# esp8266-board.net
KiCad netlist of a schematic drawn in EAGLE
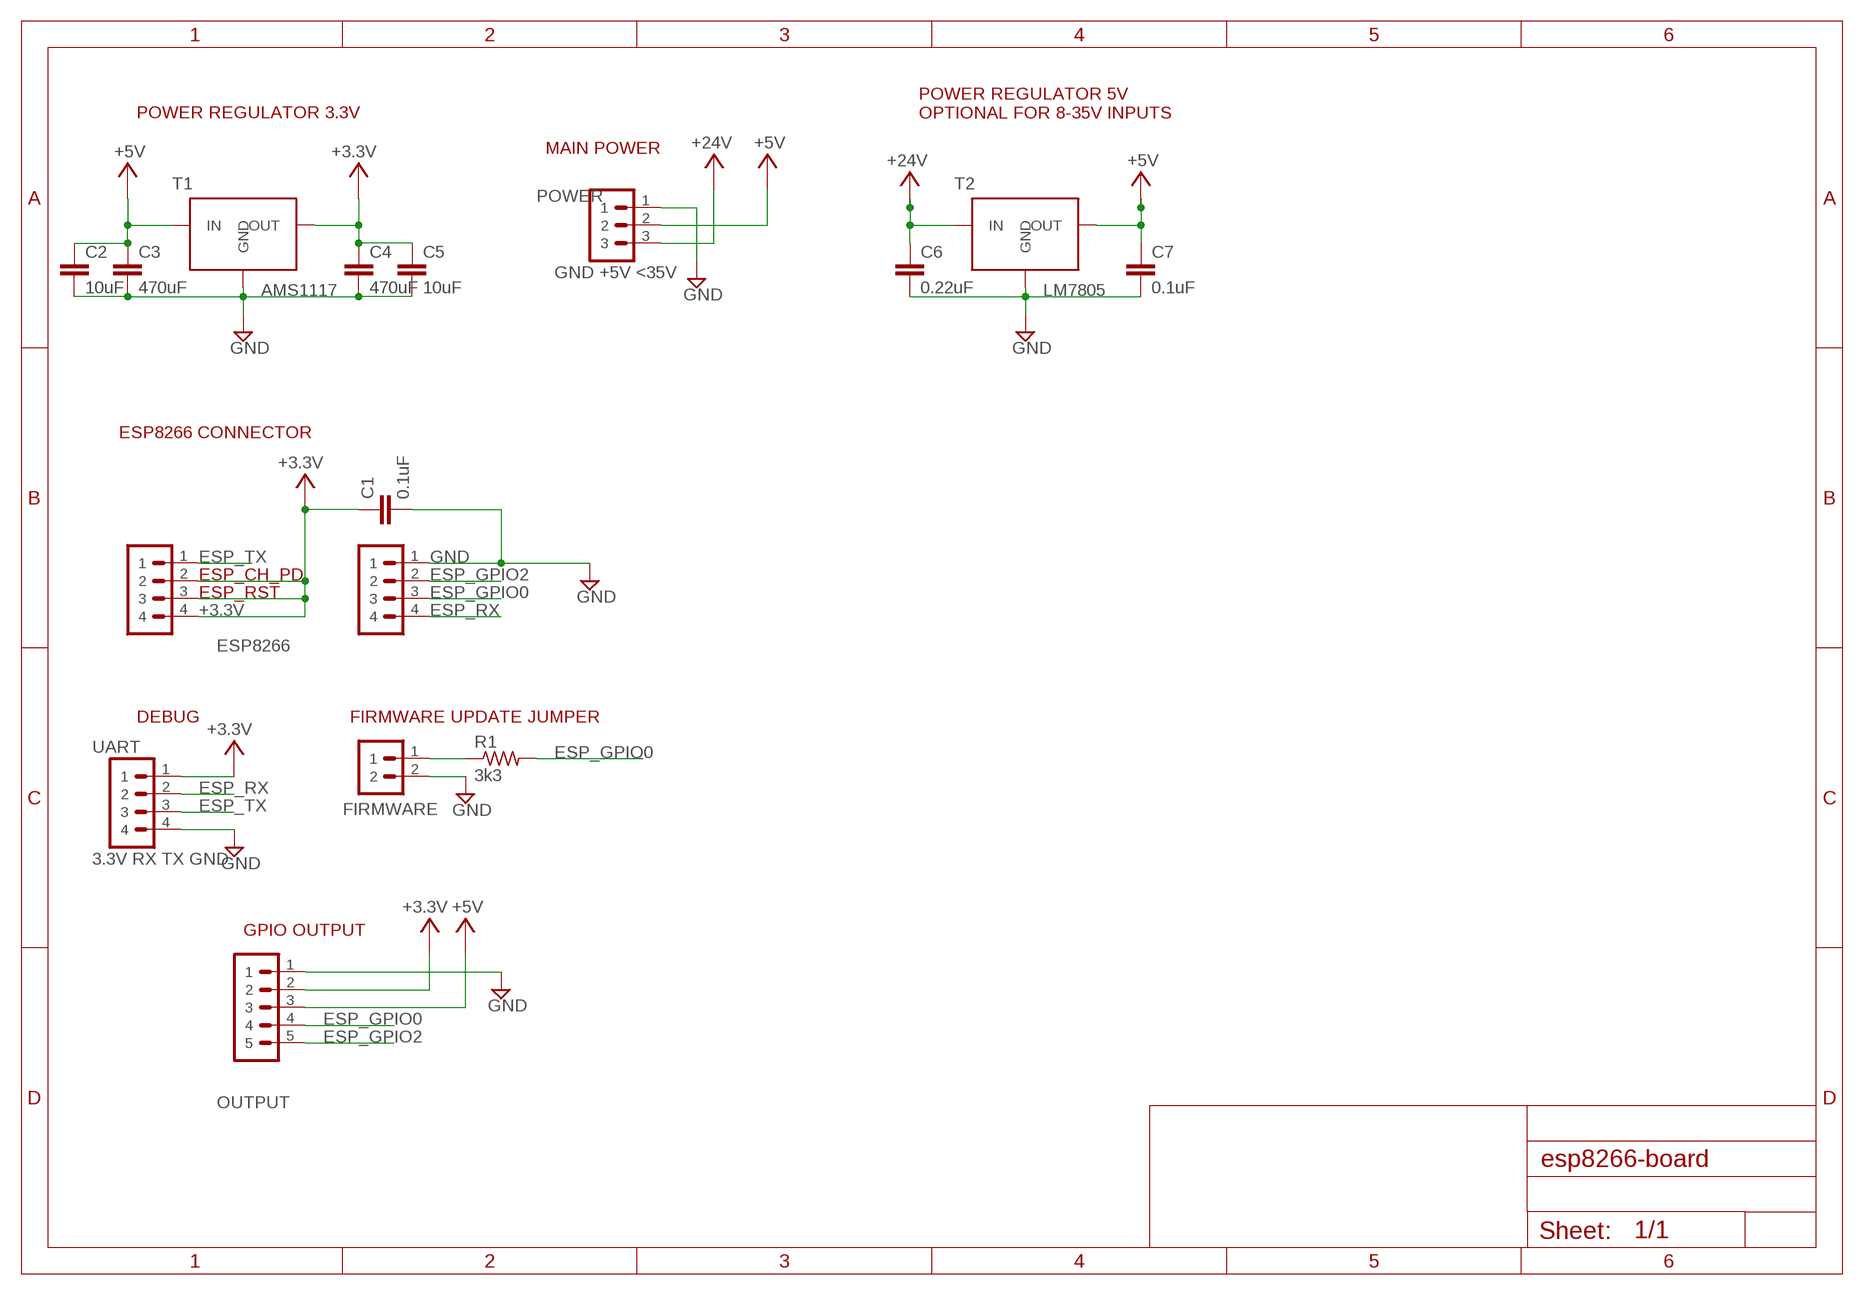
[diagram p0: schematic, sheet 1]

(export (version "E")
  (design (tool "Eeschema 10.0.6"))
  (components
    (comp (ref "C1")
      (value "0.1uF")
      (footprint "eagle-import:C2.5-2")
      (libsource (lib "eagle-import") (part "C2.5/2"))
    )
    (comp (ref "C2")
      (value "10uF")
      (footprint "eagle-import:C2.5-2")
      (libsource (lib "eagle-import") (part "C2.5/2"))
    )
    (comp (ref "C3")
      (value "470uF")
      (footprint "eagle-import:C2.5-2")
      (fields (field (name "MPN") "1C10Z5U104M050B"))
      (libsource (lib "eagle-import") (part "C2.5/2"))
    )
    (comp (ref "C4")
      (value "470uF")
      (footprint "eagle-import:C2.5-2")
      (fields (field (name "MPN") "FK18X5R0J106M"))
      (libsource (lib "eagle-import") (part "C2.5/2"))
    )
    (comp (ref "C5")
      (value "10uF")
      (footprint "eagle-import:C2.5-2")
      (libsource (lib "eagle-import") (part "C2.5/2"))
    )
    (comp (ref "C6")
      (value "0.22uF")
      (footprint "eagle-import:C2.5-2")
      (fields (field (name "MPN") "1C10Z5U104M050B"))
      (libsource (lib "eagle-import") (part "C2.5/2"))
    )
    (comp (ref "C7")
      (value "0.1uF")
      (footprint "eagle-import:C2.5-2")
      (fields (field (name "MPN") "FK18X5R0J106M"))
      (libsource (lib "eagle-import") (part "C2.5/2"))
    )
    (comp (ref "FIRMWARE")
      (value "FIRMWARE")
      (footprint "eagle-import:PIN-HEADER-2PIN")
      (libsource (lib "eagle-import") (part "PIN-HEADER-2PIN"))
    )
    (comp (ref "OUTPUT")
      (value "GND 3.3V 5V IO0 IO2")
      (footprint "eagle-import:PIN-HEADER-5PIN")
      (libsource (lib "eagle-import") (part "PIN-HEADER-5PIN"))
    )
    (comp (ref "P1")
      (value "ESP8266")
      (footprint "eagle-import:PIN-HEADER-4PIN")
      (libsource (lib "eagle-import") (part "PIN-HEADER-4PIN"))
    )
    (comp (ref "P2")
      (value "ESP8266 CONNECTOR")
      (footprint "eagle-import:PIN-HEADER-4PIN")
      (libsource (lib "eagle-import") (part "PIN-HEADER-4PIN"))
    )
    (comp (ref "POWER")
      (value "GND +5V <35V")
      (footprint "eagle-import:PIN-HEADER-3PIN")
      (libsource (lib "eagle-import") (part "PIN-HEADER-3PIN"))
    )
    (comp (ref "R1")
      (value "3k3")
      (footprint "eagle-import:RESISTOR-V3")
      (libsource (lib "eagle-import") (part "RESISTORV3"))
    )
    (comp (ref "T1")
      (value "AMS1117")
      (footprint "eagle-import:SOT-223")
      (fields (field (name "MPN") "LM2937ET-3.3"))
      (libsource (lib "eagle-import") (part "AMS1117"))
    )
    (comp (ref "T2")
      (value "LM7805")
      (footprint "eagle-import:TO-220")
      (fields (field (name "MPN") "LM2937ET-3.3"))
      (libsource (lib "eagle-import") (part "LM7805"))
    )
    (comp (ref "UART")
      (value "3.3V RX TX GND")
      (footprint "eagle-import:PIN-HEADER-4PIN")
      (libsource (lib "eagle-import") (part "PIN-HEADER-4PIN"))
    )
  )
  (nets
    (net (code "1") (name "+3.3V") (class "Default")
      (node (ref "C1") (pin "1") (pinfunction "1_1") (pintype "passive"))
      (node (ref "C4") (pin "1") (pinfunction "1_1") (pintype "passive"))
      (node (ref "C5") (pin "1") (pinfunction "1_1") (pintype "passive"))
      (node (ref "OUTPUT") (pin "2") (pinfunction "2_2") (pintype "passive"))
      (node (ref "P1") (pin "2") (pinfunction "2_2") (pintype "passive"))
      (node (ref "P1") (pin "3") (pinfunction "3_3") (pintype "passive"))
      (node (ref "P1") (pin "4") (pinfunction "4_4") (pintype "passive"))
      (node (ref "T1") (pin "2") (pinfunction "OUT_2") (pintype "power_in"))
      (node (ref "UART") (pin "1") (pinfunction "1_1") (pintype "passive"))
    )
    (net (code "2") (name "+5V") (class "Default")
      (node (ref "C2") (pin "1") (pinfunction "1_1") (pintype "passive"))
      (node (ref "C3") (pin "1") (pinfunction "1_1") (pintype "passive"))
      (node (ref "C7") (pin "1") (pinfunction "1_1") (pintype "passive"))
      (node (ref "OUTPUT") (pin "3") (pinfunction "3_3") (pintype "passive"))
      (node (ref "POWER") (pin "2") (pinfunction "2_2") (pintype "passive"))
      (node (ref "T1") (pin "3") (pinfunction "IN_3") (pintype "power_in"))
      (node (ref "T2") (pin "OUTPUT") (pinfunction "OUT_OUTPUT") (pintype "power_in"))
    )
    (net (code "3") (name "+24V") (class "Default")
      (node (ref "C6") (pin "1") (pinfunction "1_1") (pintype "passive"))
      (node (ref "POWER") (pin "3") (pinfunction "3_3") (pintype "passive"))
      (node (ref "T2") (pin "INPUT") (pinfunction "IN_INPUT") (pintype "power_in"))
    )
    (net (code "4") (name "/ESP_GPIO0") (class "Default")
      (node (ref "OUTPUT") (pin "4") (pinfunction "4_4") (pintype "passive"))
      (node (ref "P2") (pin "3") (pinfunction "3_3") (pintype "passive"))
      (node (ref "R1") (pin "2") (pinfunction "2_2") (pintype "passive"))
    )
    (net (code "5") (name "/ESP_GPIO2") (class "Default")
      (node (ref "OUTPUT") (pin "5") (pinfunction "5_5") (pintype "passive"))
      (node (ref "P2") (pin "2") (pinfunction "2_2") (pintype "passive"))
    )
    (net (code "6") (name "/ESP_RX") (class "Default")
      (node (ref "P2") (pin "4") (pinfunction "4_4") (pintype "passive"))
      (node (ref "UART") (pin "2") (pinfunction "2_2") (pintype "passive"))
    )
    (net (code "7") (name "/ESP_TX") (class "Default")
      (node (ref "P1") (pin "1") (pinfunction "1_1") (pintype "passive"))
      (node (ref "UART") (pin "3") (pinfunction "3_3") (pintype "passive"))
    )
    (net (code "8") (name "GND") (class "Default")
      (node (ref "C1") (pin "2") (pinfunction "2_2") (pintype "passive"))
      (node (ref "C2") (pin "2") (pinfunction "2_2") (pintype "passive"))
      (node (ref "C3") (pin "2") (pinfunction "2_2") (pintype "passive"))
      (node (ref "C4") (pin "2") (pinfunction "2_2") (pintype "passive"))
      (node (ref "C5") (pin "2") (pinfunction "2_2") (pintype "passive"))
      (node (ref "C6") (pin "2") (pinfunction "2_2") (pintype "passive"))
      (node (ref "C7") (pin "2") (pinfunction "2_2") (pintype "passive"))
      (node (ref "FIRMWARE") (pin "2") (pinfunction "2_2") (pintype "passive"))
      (node (ref "OUTPUT") (pin "1") (pinfunction "1_1") (pintype "passive"))
      (node (ref "P2") (pin "1") (pinfunction "1_1") (pintype "passive"))
      (node (ref "POWER") (pin "1") (pinfunction "1_1") (pintype "passive"))
      (node (ref "T1") (pin "1") (pinfunction "GND_1") (pintype "power_in"))
      (node (ref "T2") (pin "GND") (pinfunction "GND_GND") (pintype "power_in"))
      (node (ref "UART") (pin "4") (pinfunction "4_4") (pintype "passive"))
    )
    (net (code "9") (name "Net-(FIRMWARE-Pad1)") (class "Default")
      (node (ref "FIRMWARE") (pin "1") (pinfunction "1_1") (pintype "passive"))
      (node (ref "R1") (pin "1") (pinfunction "1_1") (pintype "passive"))
    )
  )
)
